# uC_General.net
KiCad netlist of a schematic drawn in Altium Designer
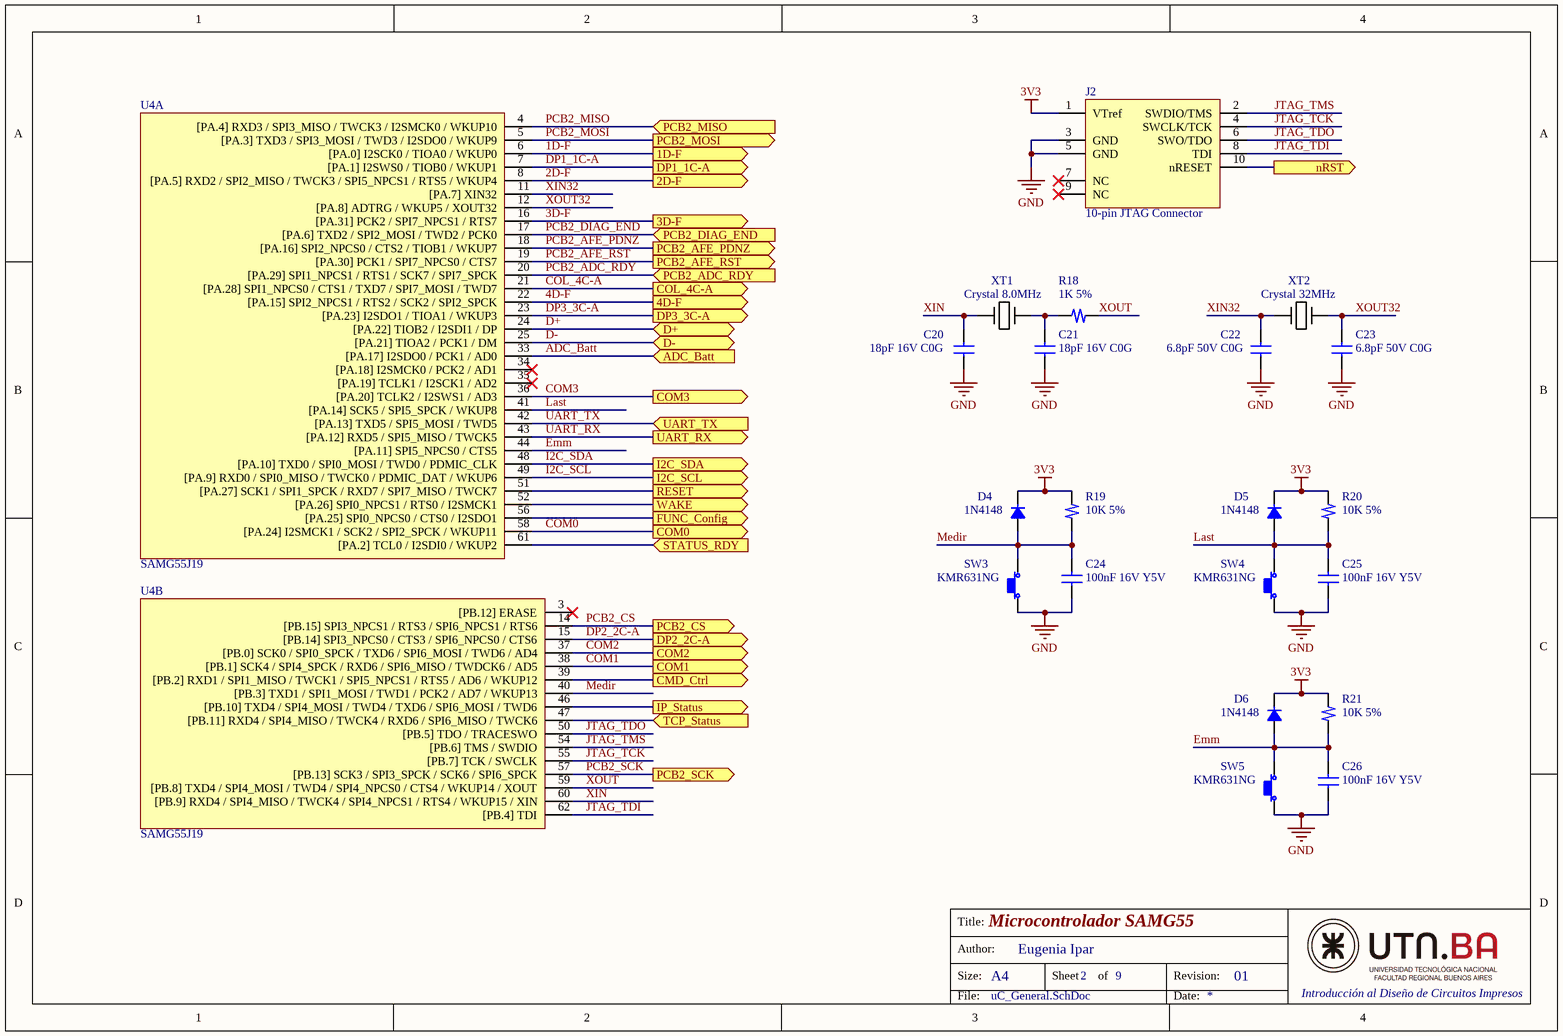
[diagram p0: uC_General.SchDoc]

(export (version "E")
  (design (tool "Eeschema 10.0.6"))
  (components
    (comp (ref "C20")
      (value "18pF 16V C0G")
      (footprint "C_0402")
      (description "Ceramic Capacitor SMD 0402")
      (libsource (lib "Oxy_Lib") (part "Ceramic Capacitor"))
    )
    (comp (ref "C21")
      (value "18pF 16V C0G")
      (footprint "C_0402")
      (description "Ceramic Capacitor SMD 0402")
      (libsource (lib "Oxy_Lib") (part "Ceramic Capacitor"))
    )
    (comp (ref "C22")
      (value "6.8pF 50V C0G")
      (footprint "C_0402")
      (description "Ceramic Capacitor SMD 0402")
      (libsource (lib "Oxy_Lib") (part "Ceramic Capacitor"))
    )
    (comp (ref "C23")
      (value "6.8pF 50V C0G")
      (footprint "C_0402")
      (description "Ceramic Capacitor SMD 0402")
      (libsource (lib "Oxy_Lib") (part "Ceramic Capacitor"))
    )
    (comp (ref "C24")
      (value "100nF 16V Y5V")
      (footprint "C_0402")
      (description "Ceramic Capacitor SMD 0402")
      (libsource (lib "Oxy_Lib") (part "Ceramic Capacitor"))
    )
    (comp (ref "C25")
      (value "100nF 16V Y5V")
      (footprint "C_0402")
      (description "Ceramic Capacitor SMD 0402")
      (libsource (lib "Oxy_Lib") (part "Ceramic Capacitor"))
    )
    (comp (ref "C26")
      (value "100nF 16V Y5V")
      (footprint "C_0402")
      (description "Ceramic Capacitor SMD 0402")
      (libsource (lib "Oxy_Lib") (part "Ceramic Capacitor"))
    )
    (comp (ref "D4")
      (value "1N4148")
      (footprint "SOD523")
      (description "Diode 1N4148 SMD SOD523")
      (libsource (lib "Oxy_Lib") (part "Diode 1N4148"))
    )
    (comp (ref "D5")
      (value "1N4148")
      (footprint "SOD523")
      (description "Diode 1N4148 SMD SOD523")
      (libsource (lib "Oxy_Lib") (part "Diode 1N4148"))
    )
    (comp (ref "D6")
      (value "1N4148")
      (footprint "SOD523")
      (description "Diode 1N4148 SMD SOD523")
      (libsource (lib "Oxy_Lib") (part "Diode 1N4148"))
    )
    (comp (ref "J2")
      (value "10-pin JTAG Connector")
      (footprint "JTAG HEADER")
      (description "JTAG Connector Micro Terminal Strip .050\" 10pin 2row")
      (libsource (lib "Oxy_Lib") (part "JTAG Connector"))
    )
    (comp (ref "R18")
      (value "1K 5%")
      (footprint "R_0402")
      (description "Resistor SMD 0402")
      (libsource (lib "Oxy_Lib") (part "Resistor"))
    )
    (comp (ref "R19")
      (value "10K 5%")
      (footprint "R_0402")
      (description "Resistor SMD 0402")
      (libsource (lib "Oxy_Lib") (part "Resistor"))
    )
    (comp (ref "R20")
      (value "10K 5%")
      (footprint "R_0402")
      (description "Resistor SMD 0402")
      (libsource (lib "Oxy_Lib") (part "Resistor"))
    )
    (comp (ref "R21")
      (value "10K 5%")
      (footprint "R_0402")
      (description "Resistor SMD 0402")
      (libsource (lib "Oxy_Lib") (part "Resistor"))
    )
    (comp (ref "SW3")
      (value "KMR631NG")
      (footprint "TACT SWITCH")
      (description "Tact Switch")
      (libsource (lib "Oxy_Lib") (part "Tact Switch"))
    )
    (comp (ref "SW4")
      (value "KMR631NG")
      (footprint "TACT SWITCH")
      (description "Tact Switch")
      (libsource (lib "Oxy_Lib") (part "Tact Switch"))
    )
    (comp (ref "SW5")
      (value "KMR631NG")
      (footprint "TACT SWITCH")
      (description "Tact Switch")
      (libsource (lib "Oxy_Lib") (part "Tact Switch"))
    )
    (comp (ref "U4")
      (value "SAMG55J19")
      (footprint "LQFP 64")
      (description "Atmel SMART SAM G55 Cortex M4 32-bit 64-lead LQFP")
      (libsource (lib "Oxy_Lib") (part "SAMG55J19"))
    )
    (comp (ref "XT1")
      (value "Crystal 8.0MHz")
      (footprint "CRYSTAL_8")
      (description "Crystal Oscillator 8.0MHz 20ppm 18pF PN: ABM7-8.000MHZ-D2Y-T")
      (libsource (lib "Oxy_Lib") (part "Crystal 8MHz"))
    )
    (comp (ref "XT2")
      (value "Crystal 32MHz")
      (footprint "FC-135")
      (description "Crystal Oscillator 32.768KHz 20ppm 7.0 pF PN: FC-135 32.7680KA-AG0")
      (libsource (lib "Oxy_Lib") (part "Crystal 32MHz"))
    )
  )
  (nets
    (net (code "1") (name "/1D-F") (class "Default")
      (node (ref "U4") (pin "6") (pinfunction "[PA.0]_I2SCK0_/_TIOA0_/_WKUP0_6") (pintype "passive"))
    )
    (net (code "2") (name "/2D-F") (class "Default")
      (node (ref "U4") (pin "8") (pinfunction "[PA.5]_RXD2_/_SPI2_MISO_/_TWCK3_/_SPI5_NPCS1_/_RTS5_/_WKUP4_8") (pintype "passive"))
    )
    (net (code "3") (name "/3D-F") (class "Default")
      (node (ref "U4") (pin "16") (pinfunction "[PA.31]_PCK2_/_SPI7_NPCS1_/_RTS7_16") (pintype "passive"))
    )
    (net (code "4") (name "/4D-F") (class "Default")
      (node (ref "U4") (pin "22") (pinfunction "[PA.15]_SPI2_NPCS1_/_RTS2_/_SCK2_/_SPI2_SPCK_22") (pintype "passive"))
    )
    (net (code "5") (name "/ADC_Batt") (class "Default")
      (node (ref "U4") (pin "33") (pinfunction "[PA.17]_I2SDO0_/_PCK1_/_AD0_33") (pintype "passive"))
    )
    (net (code "6") (name "/CMD_Ctrl") (class "Default")
      (node (ref "U4") (pin "39") (pinfunction "[PB.2]_RXD1_/_SPI1_MISO_/_TWCK1_/_SPI5_NPCS1_/_RTS5_/_AD6_/_WKUP12_39") (pintype "passive"))
    )
    (net (code "7") (name "/COL_4C-A") (class "Default")
      (node (ref "U4") (pin "21") (pinfunction "[PA.28]_SPI1_NPCS0_/_CTS1_/_TXD7_/_SPI7_MOSI_/_TWD7_21") (pintype "passive"))
    )
    (net (code "8") (name "/COM0") (class "Default")
      (node (ref "U4") (pin "58") (pinfunction "[PA.24]_I2SMCK1_/_SCK2_/_SPI2_SPCK_/_WKUP11_58") (pintype "passive"))
    )
    (net (code "9") (name "/COM1") (class "Default")
      (node (ref "U4") (pin "38") (pinfunction "[PB.1]_SCK4_/_SPI4_SPCK_/_RXD6_/_SPI6_MISO_/_TWDCK6_/_AD5_38") (pintype "passive"))
    )
    (net (code "10") (name "/COM2") (class "Default")
      (node (ref "U4") (pin "37") (pinfunction "[PB.0]_SCK0_/_SPI0_SPCK_/_TXD6_/_SPI6_MOSI_/_TWD6_/_AD4_37") (pintype "passive"))
    )
    (net (code "11") (name "/COM3") (class "Default")
      (node (ref "U4") (pin "36") (pinfunction "[PA.20]_TCLK2_/_I2SWS1_/_AD3_36") (pintype "passive"))
    )
    (net (code "12") (name "/D+") (class "Default")
      (node (ref "U4") (pin "24") (pinfunction "[PA.22]_TIOB2_/_I2SDI1_/_DP_24") (pintype "passive"))
    )
    (net (code "13") (name "/D-") (class "Default")
      (node (ref "U4") (pin "25") (pinfunction "[PA.21]_TIOA2_/_PCK1_/_DM_25") (pintype "passive"))
    )
    (net (code "14") (name "/DP1_1C-A") (class "Default")
      (node (ref "U4") (pin "7") (pinfunction "[PA.1]_I2SWS0_/_TIOB0_/_WKUP1_7") (pintype "passive"))
    )
    (net (code "15") (name "/DP2_2C-A") (class "Default")
      (node (ref "U4") (pin "15") (pinfunction "[PB.14]_SPI3_NPCS0_/_CTS3_/_SPI6_NPCS0_/_CTS6_15") (pintype "passive"))
    )
    (net (code "16") (name "/DP3_3C-A") (class "Default")
      (node (ref "U4") (pin "23") (pinfunction "[PA.23]_I2SDO1_/_TIOA1_/_WKUP3_23") (pintype "passive"))
    )
    (net (code "17") (name "/Emm") (class "Default")
      (node (ref "C26") (pin "1") (pinfunction "1_1") (pintype "passive"))
      (node (ref "D6") (pin "1") (pinfunction "1_1") (pintype "passive"))
      (node (ref "R21") (pin "1") (pinfunction "1_1") (pintype "passive"))
      (node (ref "SW5") (pin "2") (pinfunction "2_2") (pintype "passive"))
      (node (ref "U4") (pin "44") (pinfunction "[PA.11]_SPI5_NPCS0_/_CTS5_44") (pintype "passive"))
    )
    (net (code "18") (name "/FUNC_Config") (class "Default")
      (node (ref "U4") (pin "56") (pinfunction "[PA.25]_SPI0_NPCS0_/_CTS0_/_I2SDO1_56") (pintype "passive"))
    )
    (net (code "19") (name "/I2C_SCL") (class "Default")
      (node (ref "U4") (pin "49") (pinfunction "[PA.9]_RXD0_/_SPI0_MISO_/_TWCK0_/_PDMIC_DAT_/_WKUP6_49") (pintype "passive"))
    )
    (net (code "20") (name "/I2C_SDA") (class "Default")
      (node (ref "U4") (pin "48") (pinfunction "[PA.10]_TXD0_/_SPI0_MOSI_/_TWD0_/_PDMIC_CLK_48") (pintype "passive"))
    )
    (net (code "21") (name "/IP_Status") (class "Default")
      (node (ref "U4") (pin "46") (pinfunction "[PB.10]_TXD4_/_SPI4_MOSI_/_TWD4_/_TXD6_/_SPI6_MOSI_/_TWD6_46") (pintype "passive"))
    )
    (net (code "22") (name "/JTAG_TCK") (class "Default")
      (node (ref "J2") (pin "4") (pinfunction "SWCLK/TCK_4") (pintype "passive"))
      (node (ref "U4") (pin "55") (pinfunction "[PB.7]_TCK_/_SWCLK_55") (pintype "passive"))
    )
    (net (code "23") (name "/JTAG_TDI") (class "Default")
      (node (ref "J2") (pin "8") (pinfunction "TDI_8") (pintype "passive"))
      (node (ref "U4") (pin "62") (pinfunction "[PB.4]_TDI_62") (pintype "passive"))
    )
    (net (code "24") (name "/JTAG_TDO") (class "Default")
      (node (ref "J2") (pin "6") (pinfunction "SWO/TDO_6") (pintype "passive"))
      (node (ref "U4") (pin "50") (pinfunction "[PB.5]_TDO_/_TRACESWO_50") (pintype "passive"))
    )
    (net (code "25") (name "/JTAG_TMS") (class "Default")
      (node (ref "J2") (pin "2") (pinfunction "SWDIO/TMS_2") (pintype "passive"))
      (node (ref "U4") (pin "54") (pinfunction "[PB.6]_TMS_/_SWDIO_54") (pintype "passive"))
    )
    (net (code "26") (name "/Last") (class "Default")
      (node (ref "C25") (pin "1") (pinfunction "1_1") (pintype "passive"))
      (node (ref "D5") (pin "1") (pinfunction "1_1") (pintype "passive"))
      (node (ref "R20") (pin "1") (pinfunction "1_1") (pintype "passive"))
      (node (ref "SW4") (pin "2") (pinfunction "2_2") (pintype "passive"))
      (node (ref "U4") (pin "41") (pinfunction "[PA.14]_SCK5_/_SPI5_SPCK_/_WKUP8_41") (pintype "passive"))
    )
    (net (code "27") (name "/Medir") (class "Default")
      (node (ref "C24") (pin "1") (pinfunction "1_1") (pintype "passive"))
      (node (ref "D4") (pin "1") (pinfunction "1_1") (pintype "passive"))
      (node (ref "R19") (pin "1") (pinfunction "1_1") (pintype "passive"))
      (node (ref "SW3") (pin "2") (pinfunction "2_2") (pintype "passive"))
      (node (ref "U4") (pin "40") (pinfunction "[PB.3]_TXD1_/_SPI1_MOSI_/_TWD1_/_PCK2_/_AD7_/_WKUP13_40") (pintype "passive"))
    )
    (net (code "28") (name "/PCB2_ADC_RDY") (class "Default")
      (node (ref "U4") (pin "20") (pinfunction "[PA.29]_SPI1_NPCS1_/_RTS1_/_SCK7_/_SPI7_SPCK_20") (pintype "passive"))
    )
    (net (code "29") (name "/PCB2_AFE_PDNZ") (class "Default")
      (node (ref "U4") (pin "18") (pinfunction "[PA.16]_SPI2_NPCS0_/_CTS2_/_TIOB1_/_WKUP7_18") (pintype "passive"))
    )
    (net (code "30") (name "/PCB2_AFE_RST") (class "Default")
      (node (ref "U4") (pin "19") (pinfunction "[PA.30]_PCK1_/_SPI7_NPCS0_/_CTS7_19") (pintype "passive"))
    )
    (net (code "31") (name "/PCB2_CS") (class "Default")
      (node (ref "U4") (pin "14") (pinfunction "[PB.15]_SPI3_NPCS1_/_RTS3_/_SPI6_NPCS1_/_RTS6_14") (pintype "passive"))
    )
    (net (code "32") (name "/PCB2_DIAG_END") (class "Default")
      (node (ref "U4") (pin "17") (pinfunction "[PA.6]_TXD2_/_SPI2_MOSI_/_TWD2_/_PCK0_17") (pintype "passive"))
    )
    (net (code "33") (name "/PCB2_MISO") (class "Default")
      (node (ref "U4") (pin "4") (pinfunction "[PA.4]_RXD3_/_SPI3_MISO_/_TWCK3_/_I2SMCK0_/_WKUP10_4") (pintype "passive"))
    )
    (net (code "34") (name "/PCB2_MOSI") (class "Default")
      (node (ref "U4") (pin "5") (pinfunction "[PA.3]_TXD3_/_SPI3_MOSI_/_TWD3_/_I2SDO0_/_WKUP9_5") (pintype "passive"))
    )
    (net (code "35") (name "/PCB2_SCK") (class "Default")
      (node (ref "U4") (pin "57") (pinfunction "[PB.13]_SCK3_/_SPI3_SPCK_/_SCK6_/_SPI6_SPCK_57") (pintype "passive"))
    )
    (net (code "36") (name "/RESET") (class "Default")
      (node (ref "U4") (pin "51") (pinfunction "[PA.27]_SCK1_/_SPI1_SPCK_/_RXD7_/_SPI7_MISO_/_TWCK7_51") (pintype "passive"))
    )
    (net (code "37") (name "/STATUS_RDY") (class "Default")
      (node (ref "U4") (pin "61") (pinfunction "[PA.2]_TCL0_/_I2SDI0_/_WKUP2_61") (pintype "passive"))
    )
    (net (code "38") (name "/TCP_Status") (class "Default")
      (node (ref "U4") (pin "47") (pinfunction "[PB.11]_RXD4_/_SPI4_MISO_/_TWCK4_/_RXD6_/_SPI6_MISO_/_TWCK6_47") (pintype "passive"))
    )
    (net (code "39") (name "/UART_RX") (class "Default")
      (node (ref "U4") (pin "43") (pinfunction "[PA.12]_RXD5_/_SPI5_MISO_/_TWCK5_43") (pintype "passive"))
    )
    (net (code "40") (name "/UART_TX") (class "Default")
      (node (ref "U4") (pin "42") (pinfunction "[PA.13]_TXD5_/_SPI5_MOSI_/_TWD5_42") (pintype "passive"))
    )
    (net (code "41") (name "/WAKE") (class "Default")
      (node (ref "U4") (pin "52") (pinfunction "[PA.26]_SPI0_NPCS1_/_RTS0_/_I2SMCK1_52") (pintype "passive"))
    )
    (net (code "42") (name "/XIN") (class "Default")
      (node (ref "C20") (pin "1") (pinfunction "1_1") (pintype "passive"))
      (node (ref "U4") (pin "60") (pinfunction "[PB.9]_RXD4_/_SPI4_MISO_/_TWCK4_/_SPI4_NPCS1_/_RTS4_/_WKUP15_/_XIN_60") (pintype "passive"))
      (node (ref "XT1") (pin "1") (pinfunction "IN_1") (pintype "passive"))
    )
    (net (code "43") (name "/XIN32") (class "Default")
      (node (ref "C22") (pin "1") (pinfunction "1_1") (pintype "passive"))
      (node (ref "U4") (pin "11") (pinfunction "[PA.7]_XIN32_11") (pintype "passive"))
      (node (ref "XT2") (pin "1") (pinfunction "IN_1") (pintype "passive"))
    )
    (net (code "44") (name "/XOUT") (class "Default")
      (node (ref "R18") (pin "2") (pinfunction "2_2") (pintype "passive"))
      (node (ref "U4") (pin "59") (pinfunction "[PB.8]_TXD4_/_SPI4_MOSI_/_TWD4_/_SPI4_NPCS0_/_CTS4_/_WKUP14_/_XOUT_59") (pintype "passive"))
    )
    (net (code "45") (name "/XOUT32") (class "Default")
      (node (ref "C23") (pin "1") (pinfunction "1_1") (pintype "passive"))
      (node (ref "U4") (pin "12") (pinfunction "[PA.8]_ADTRG_/_WKUP5_/_XOUT32_12") (pintype "passive"))
      (node (ref "XT2") (pin "2") (pinfunction "OUT_2") (pintype "passive"))
    )
    (net (code "46") (name "/nRST") (class "Default")
      (node (ref "J2") (pin "10") (pinfunction "nRESET_10") (pintype "passive"))
    )
    (net (code "47") (name "3V3") (class "Default")
      (node (ref "D4") (pin "2") (pinfunction "2_2") (pintype "passive"))
      (node (ref "D5") (pin "2") (pinfunction "2_2") (pintype "passive"))
      (node (ref "D6") (pin "2") (pinfunction "2_2") (pintype "passive"))
      (node (ref "J2") (pin "1") (pinfunction "VTref_1") (pintype "passive"))
      (node (ref "R19") (pin "2") (pinfunction "2_2") (pintype "passive"))
      (node (ref "R20") (pin "2") (pinfunction "2_2") (pintype "passive"))
      (node (ref "R21") (pin "2") (pinfunction "2_2") (pintype "passive"))
    )
    (net (code "48") (name "GND") (class "Default")
      (node (ref "C20") (pin "2") (pinfunction "2_2") (pintype "passive"))
      (node (ref "C21") (pin "2") (pinfunction "2_2") (pintype "passive"))
      (node (ref "C22") (pin "2") (pinfunction "2_2") (pintype "passive"))
      (node (ref "C23") (pin "2") (pinfunction "2_2") (pintype "passive"))
      (node (ref "C24") (pin "2") (pinfunction "2_2") (pintype "passive"))
      (node (ref "C25") (pin "2") (pinfunction "2_2") (pintype "passive"))
      (node (ref "C26") (pin "2") (pinfunction "2_2") (pintype "passive"))
      (node (ref "J2") (pin "3") (pinfunction "GND_3") (pintype "passive"))
      (node (ref "J2") (pin "5") (pinfunction "GND_5") (pintype "passive"))
      (node (ref "SW3") (pin "1") (pinfunction "1_1") (pintype "passive"))
      (node (ref "SW4") (pin "1") (pinfunction "1_1") (pintype "passive"))
      (node (ref "SW5") (pin "1") (pinfunction "1_1") (pintype "passive"))
    )
    (net (code "49") (name "Net-(XT1-OUT)") (class "Default")
      (node (ref "C21") (pin "1") (pinfunction "1_1") (pintype "passive"))
      (node (ref "R18") (pin "1") (pinfunction "1_1") (pintype "passive"))
      (node (ref "XT1") (pin "2") (pinfunction "OUT_2") (pintype "passive"))
    )
    (net (code "50") (name "unconnected-(J2-NC-Pad7)") (class "Default")
      (node (ref "J2") (pin "7") (pinfunction "NC_7") (pintype "passive+no_connect"))
    )
    (net (code "51") (name "unconnected-(J2-NC-Pad9)") (class "Default")
      (node (ref "J2") (pin "9") (pinfunction "NC_9") (pintype "passive+no_connect"))
    )
    (net (code "52") (name "unconnected-(U4A-[PA.18]_I2SMCK0_{slash}_PCK2_{slash}_AD1-Pad34)") (class "Default")
      (node (ref "U4") (pin "34") (pinfunction "[PA.18]_I2SMCK0_/_PCK2_/_AD1_34") (pintype "passive+no_connect"))
    )
    (net (code "53") (name "unconnected-(U4A-[PA.19]_TCLK1_{slash}_I2SCK1_{slash}_AD2-Pad35)") (class "Default")
      (node (ref "U4") (pin "35") (pinfunction "[PA.19]_TCLK1_/_I2SCK1_/_AD2_35") (pintype "passive+no_connect"))
    )
    (net (code "54") (name "unconnected-(U4B-[PB.12]_ERASE-Pad3)") (class "Default")
      (node (ref "U4") (pin "3") (pinfunction "[PB.12]_ERASE_3") (pintype "passive+no_connect"))
    )
  )
)
